# MegaShield-thruhole.net
KiCad netlist of a schematic drawn in EAGLE
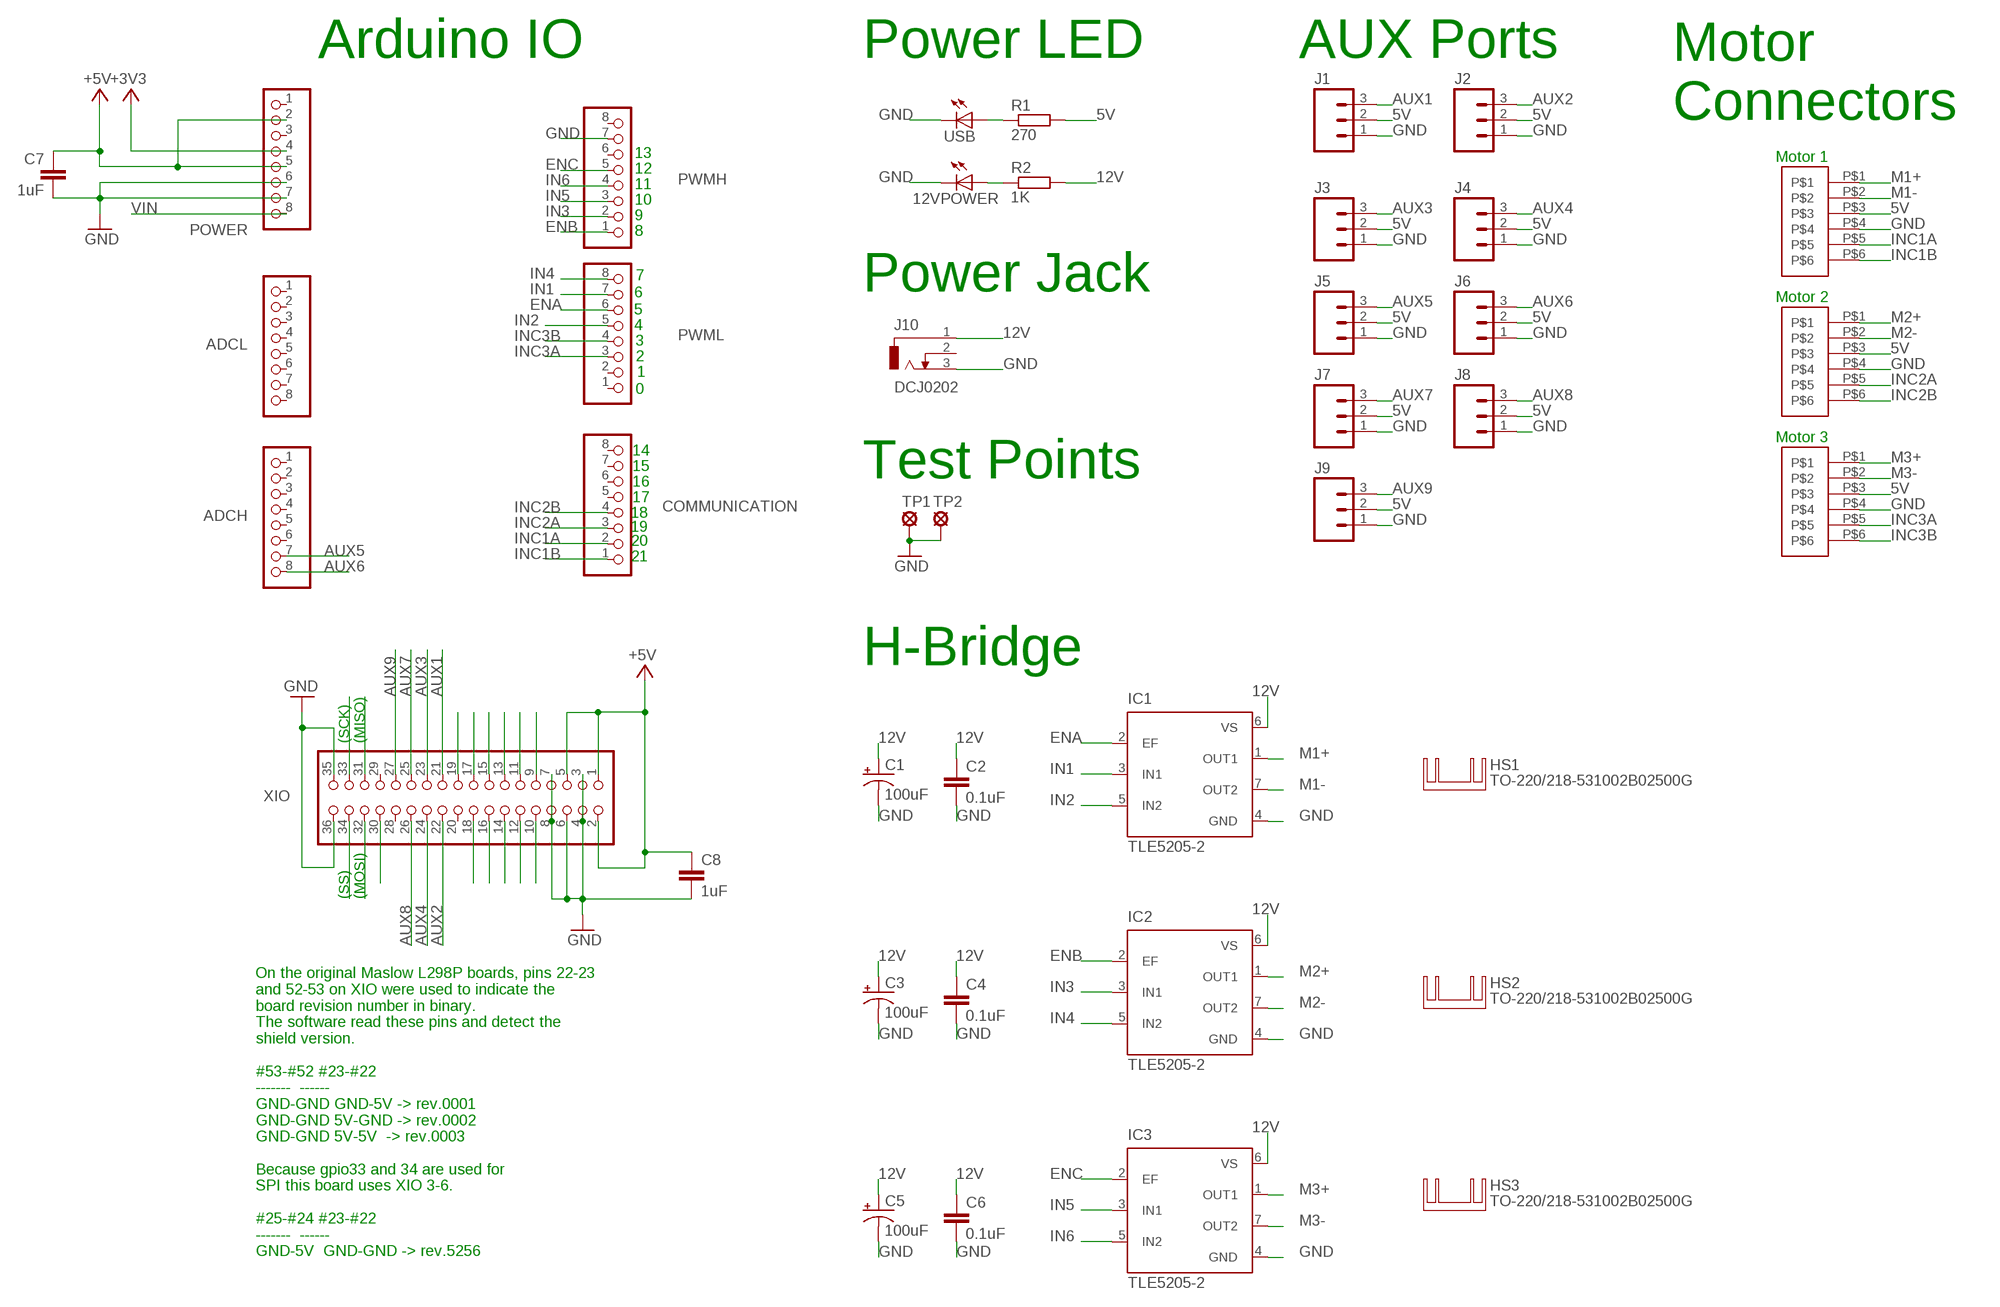
[diagram p0: schematic, sheet 1]

(export (version "E")
  (design (tool "Eeschema 10.0.6"))
  (components
    (comp (ref "12VPOWER")
      (value "LED_ELD260")
      (footprint "eagle-import:LED_LD260")
      (libsource (lib "eagle-import") (part "LED_ELD260"))
    )
    (comp (ref "ADCH")
      (value "8x1F-H8.5")
      (footprint "eagle-import:1X08")
      (libsource (lib "eagle-import") (part "PINHD-1X8"))
    )
    (comp (ref "ADCL")
      (value "PINHD-1X8")
      (footprint "eagle-import:1X08")
      (libsource (lib "eagle-import") (part "pinhead_PINHD-1X8"))
    )
    (comp (ref "C1")
      (value "100uF")
      (footprint "eagle-import:CPOL-RADIAL-100UF-25V")
      (libsource (lib "eagle-import") (part "CAP_POLPTH1"))
    )
    (comp (ref "C2")
      (value "0.1uF")
      (footprint "eagle-import:CAP-PTH-SMALL")
      (libsource (lib "eagle-import") (part "CAPPTH"))
    )
    (comp (ref "C3")
      (value "100uF")
      (footprint "eagle-import:CPOL-RADIAL-100UF-25V")
      (libsource (lib "eagle-import") (part "CAP_POLPTH1"))
    )
    (comp (ref "C4")
      (value "0.1uF")
      (footprint "eagle-import:CAP-PTH-SMALL")
      (libsource (lib "eagle-import") (part "CAPPTH"))
    )
    (comp (ref "C5")
      (value "100uF")
      (footprint "eagle-import:CPOL-RADIAL-100UF-25V")
      (libsource (lib "eagle-import") (part "CAP_POLPTH1"))
    )
    (comp (ref "C6")
      (value "0.1uF")
      (footprint "eagle-import:CAP-PTH-SMALL")
      (libsource (lib "eagle-import") (part "CAPPTH"))
    )
    (comp (ref "C7")
      (value "1uF")
      (footprint "eagle-import:CAP-PTH-SMALL")
      (libsource (lib "eagle-import") (part "CAPPTH"))
    )
    (comp (ref "C8")
      (value "1uF")
      (footprint "eagle-import:CAP-PTH-SMALL")
      (libsource (lib "eagle-import") (part "CAPPTH"))
    )
    (comp (ref "COMMUNICATION")
      (value "PINHD-1X8")
      (footprint "eagle-import:1X08")
      (libsource (lib "eagle-import") (part "pinhead_PINHD-1X8"))
    )
    (comp (ref "HS1")
      (value "TO-220/218-531002B02500G")
      (footprint "eagle-import:531XXXXXXXX")
      (libsource (lib "eagle-import") (part "TO-220/218-531XXXXXXXX"))
    )
    (comp (ref "HS2")
      (value "TO-220/218-531002B02500G")
      (footprint "eagle-import:531XXXXXXXX")
      (libsource (lib "eagle-import") (part "TO-220/218-531XXXXXXXX"))
    )
    (comp (ref "HS3")
      (value "TO-220/218-531002B02500G")
      (footprint "eagle-import:531XXXXXXXX")
      (libsource (lib "eagle-import") (part "TO-220/218-531XXXXXXXX"))
    )
    (comp (ref "IC1")
      (value "TLE5205-2")
      (footprint "eagle-import:P-TO220-7-11")
      (libsource (lib "eagle-import") (part "TLE5205-2"))
    )
    (comp (ref "IC2")
      (value "TLE5205-2")
      (footprint "eagle-import:P-TO220-7-11")
      (libsource (lib "eagle-import") (part "TLE5205-2"))
    )
    (comp (ref "IC3")
      (value "TLE5205-2")
      (footprint "eagle-import:P-TO220-7-11")
      (libsource (lib "eagle-import") (part "TLE5205-2"))
    )
    (comp (ref "J1")
      (value "M03LOCK")
      (footprint "eagle-import:1X03_LOCK")
      (libsource (lib "eagle-import") (part "M03LOCK"))
    )
    (comp (ref "J2")
      (value "M03LOCK")
      (footprint "eagle-import:1X03_LOCK")
      (libsource (lib "eagle-import") (part "M03LOCK"))
    )
    (comp (ref "J3")
      (value "M03LOCK")
      (footprint "eagle-import:1X03_LOCK")
      (libsource (lib "eagle-import") (part "M03LOCK"))
    )
    (comp (ref "J4")
      (value "M03LOCK")
      (footprint "eagle-import:1X03_LOCK")
      (libsource (lib "eagle-import") (part "M03LOCK"))
    )
    (comp (ref "J5")
      (value "M03LOCK")
      (footprint "eagle-import:1X03_LOCK")
      (libsource (lib "eagle-import") (part "M03LOCK"))
    )
    (comp (ref "J6")
      (value "M03LOCK")
      (footprint "eagle-import:1X03_LOCK")
      (libsource (lib "eagle-import") (part "M03LOCK"))
    )
    (comp (ref "J7")
      (value "M03LOCK")
      (footprint "eagle-import:1X03_LOCK")
      (libsource (lib "eagle-import") (part "M03LOCK"))
    )
    (comp (ref "J8")
      (value "M03LOCK")
      (footprint "eagle-import:1X03_LOCK")
      (libsource (lib "eagle-import") (part "M03LOCK"))
    )
    (comp (ref "J9")
      (value "M03LOCK")
      (footprint "eagle-import:1X03_LOCK")
      (libsource (lib "eagle-import") (part "M03LOCK"))
    )
    (comp (ref "J10")
      (value "DCJ0202")
      (footprint "eagle-import:DCJ0202")
      (libsource (lib "eagle-import") (part "DCJ0202"))
    )
    (comp (ref "MP1")
      (value "JST-PH-6")
      (footprint "eagle-import:JST-PHR-6-SMD")
      (libsource (lib "eagle-import") (part "JST-PH-6"))
    )
    (comp (ref "MP2")
      (value "JST-PH-6")
      (footprint "eagle-import:JST-PHR-6-SMD")
      (libsource (lib "eagle-import") (part "JST-PH-6"))
    )
    (comp (ref "MP3")
      (value "JST-PH-6")
      (footprint "eagle-import:JST-PHR-6-SMD")
      (libsource (lib "eagle-import") (part "JST-PH-6"))
    )
    (comp (ref "POWER")
      (value "8x1F-H8.5")
      (footprint "eagle-import:1X08")
      (libsource (lib "eagle-import") (part "PINHD-1X8"))
    )
    (comp (ref "PWMH")
      (value "PINHD-1X8")
      (footprint "eagle-import:1X08")
      (libsource (lib "eagle-import") (part "pinhead_PINHD-1X8"))
    )
    (comp (ref "PWML")
      (value "PINHD-1X8")
      (footprint "eagle-import:1X08")
      (libsource (lib "eagle-import") (part "pinhead_PINHD-1X8"))
    )
    (comp (ref "R1")
      (value "270")
      (footprint "eagle-import:0207_10")
      (libsource (lib "eagle-import") (part "R0207/10"))
    )
    (comp (ref "R2")
      (value "1K")
      (footprint "eagle-import:0207_10")
      (libsource (lib "eagle-import") (part "R0207/10"))
    )
    (comp (ref "TP1")
      (value "LSP10")
      (footprint "eagle-import:LSP10")
      (libsource (lib "eagle-import") (part "LSP10"))
    )
    (comp (ref "TP2")
      (value "LSP10")
      (footprint "eagle-import:LSP10")
      (libsource (lib "eagle-import") (part "LSP10"))
    )
    (comp (ref "USB")
      (value "LED_ELD260")
      (footprint "eagle-import:LED_LD260")
      (libsource (lib "eagle-import") (part "LED_ELD260"))
    )
    (comp (ref "XIO")
      (value "18x2F-H8.5")
      (footprint "eagle-import:2X18")
      (libsource (lib "eagle-import") (part "PINHD-2X18"))
    )
  )
  (nets
    (net (code "1") (name "+3V3") (class "Default")
      (node (ref "POWER") (pin "4") (pinfunction "4_4") (pintype "passive"))
    )
    (net (code "2") (name "+5V") (class "Default")
      (node (ref "C7") (pin "1") (pinfunction "1_1") (pintype "passive"))
      (node (ref "C8") (pin "1") (pinfunction "1_1") (pintype "passive"))
      (node (ref "J1") (pin "2") (pinfunction "2_2") (pintype "passive"))
      (node (ref "J2") (pin "2") (pinfunction "2_2") (pintype "passive"))
      (node (ref "J3") (pin "2") (pinfunction "2_2") (pintype "passive"))
      (node (ref "J4") (pin "2") (pinfunction "2_2") (pintype "passive"))
      (node (ref "J5") (pin "2") (pinfunction "2_2") (pintype "passive"))
      (node (ref "J6") (pin "2") (pinfunction "2_2") (pintype "passive"))
      (node (ref "J7") (pin "2") (pinfunction "2_2") (pintype "passive"))
      (node (ref "J8") (pin "2") (pinfunction "2_2") (pintype "passive"))
      (node (ref "J9") (pin "2") (pinfunction "2_2") (pintype "passive"))
      (node (ref "MP1") (pin "P$3") (pinfunction "P$3_P$3") (pintype "bidirectional"))
      (node (ref "MP2") (pin "P$3") (pinfunction "P$3_P$3") (pintype "bidirectional"))
      (node (ref "MP3") (pin "P$3") (pinfunction "P$3_P$3") (pintype "bidirectional"))
      (node (ref "POWER") (pin "2") (pinfunction "2_2") (pintype "passive"))
      (node (ref "POWER") (pin "5") (pinfunction "5_5") (pintype "passive"))
      (node (ref "R1") (pin "2") (pinfunction "2_2") (pintype "passive"))
      (node (ref "XIO") (pin "1") (pinfunction "1_1") (pintype "passive"))
      (node (ref "XIO") (pin "2") (pinfunction "2_2") (pintype "passive"))
      (node (ref "XIO") (pin "5") (pinfunction "5_5") (pintype "passive"))
    )
    (net (code "3") (name "/12V") (class "Default")
      (node (ref "C1") (pin "1") (pinfunction "+_1") (pintype "passive"))
      (node (ref "C2") (pin "1") (pinfunction "1_1") (pintype "passive"))
      (node (ref "C3") (pin "1") (pinfunction "+_1") (pintype "passive"))
      (node (ref "C4") (pin "1") (pinfunction "1_1") (pintype "passive"))
      (node (ref "C5") (pin "1") (pinfunction "+_1") (pintype "passive"))
      (node (ref "C6") (pin "1") (pinfunction "1_1") (pintype "passive"))
      (node (ref "IC1") (pin "6") (pinfunction "VS_6") (pintype "input"))
      (node (ref "IC2") (pin "6") (pinfunction "VS_6") (pintype "input"))
      (node (ref "IC3") (pin "6") (pinfunction "VS_6") (pintype "input"))
      (node (ref "J10") (pin "1") (pinfunction "1_1") (pintype "passive"))
      (node (ref "R2") (pin "2") (pinfunction "2_2") (pintype "passive"))
    )
    (net (code "4") (name "/AUX1") (class "Default")
      (node (ref "J1") (pin "3") (pinfunction "3_3") (pintype "passive"))
      (node (ref "XIO") (pin "21") (pinfunction "21_21") (pintype "passive"))
    )
    (net (code "5") (name "/AUX2") (class "Default")
      (node (ref "J2") (pin "3") (pinfunction "3_3") (pintype "passive"))
      (node (ref "XIO") (pin "22") (pinfunction "22_22") (pintype "passive"))
    )
    (net (code "6") (name "/AUX3") (class "Default")
      (node (ref "J3") (pin "3") (pinfunction "3_3") (pintype "passive"))
      (node (ref "XIO") (pin "23") (pinfunction "23_23") (pintype "passive"))
    )
    (net (code "7") (name "/AUX4") (class "Default")
      (node (ref "J4") (pin "3") (pinfunction "3_3") (pintype "passive"))
      (node (ref "XIO") (pin "24") (pinfunction "24_24") (pintype "passive"))
    )
    (net (code "8") (name "/AUX5") (class "Default")
      (node (ref "ADCH") (pin "7") (pinfunction "7_7") (pintype "passive"))
      (node (ref "J5") (pin "3") (pinfunction "3_3") (pintype "passive"))
    )
    (net (code "9") (name "/AUX6") (class "Default")
      (node (ref "ADCH") (pin "8") (pinfunction "8_8") (pintype "passive"))
      (node (ref "J6") (pin "3") (pinfunction "3_3") (pintype "passive"))
    )
    (net (code "10") (name "/AUX7") (class "Default")
      (node (ref "J7") (pin "3") (pinfunction "3_3") (pintype "passive"))
      (node (ref "XIO") (pin "25") (pinfunction "25_25") (pintype "passive"))
    )
    (net (code "11") (name "/AUX8") (class "Default")
      (node (ref "J8") (pin "3") (pinfunction "3_3") (pintype "passive"))
      (node (ref "XIO") (pin "26") (pinfunction "26_26") (pintype "passive"))
    )
    (net (code "12") (name "/AUX9") (class "Default")
      (node (ref "J9") (pin "3") (pinfunction "3_3") (pintype "passive"))
      (node (ref "XIO") (pin "27") (pinfunction "27_27") (pintype "passive"))
    )
    (net (code "13") (name "/ENA") (class "Default")
      (node (ref "IC1") (pin "2") (pinfunction "EF_2") (pintype "open_collector"))
      (node (ref "PWML") (pin "6") (pinfunction "6_6") (pintype "passive"))
    )
    (net (code "14") (name "/ENB") (class "Default")
      (node (ref "IC2") (pin "2") (pinfunction "EF_2") (pintype "open_collector"))
      (node (ref "PWMH") (pin "1") (pinfunction "1_1") (pintype "passive"))
    )
    (net (code "15") (name "/ENC") (class "Default")
      (node (ref "IC3") (pin "2") (pinfunction "EF_2") (pintype "open_collector"))
      (node (ref "PWMH") (pin "5") (pinfunction "5_5") (pintype "passive"))
    )
    (net (code "16") (name "/IN1") (class "Default")
      (node (ref "IC1") (pin "3") (pinfunction "IN1_3") (pintype "input"))
      (node (ref "PWML") (pin "7") (pinfunction "7_7") (pintype "passive"))
    )
    (net (code "17") (name "/IN2") (class "Default")
      (node (ref "IC1") (pin "5") (pinfunction "IN2_5") (pintype "input"))
      (node (ref "PWML") (pin "5") (pinfunction "5_5") (pintype "passive"))
    )
    (net (code "18") (name "/IN3") (class "Default")
      (node (ref "IC2") (pin "3") (pinfunction "IN1_3") (pintype "input"))
      (node (ref "PWMH") (pin "2") (pinfunction "2_2") (pintype "passive"))
    )
    (net (code "19") (name "/IN4") (class "Default")
      (node (ref "IC2") (pin "5") (pinfunction "IN2_5") (pintype "input"))
      (node (ref "PWML") (pin "8") (pinfunction "8_8") (pintype "passive"))
    )
    (net (code "20") (name "/IN5") (class "Default")
      (node (ref "IC3") (pin "3") (pinfunction "IN1_3") (pintype "input"))
      (node (ref "PWMH") (pin "3") (pinfunction "3_3") (pintype "passive"))
    )
    (net (code "21") (name "/IN6") (class "Default")
      (node (ref "IC3") (pin "5") (pinfunction "IN2_5") (pintype "input"))
      (node (ref "PWMH") (pin "4") (pinfunction "4_4") (pintype "passive"))
    )
    (net (code "22") (name "/INC1A") (class "Default")
      (node (ref "COMMUNICATION") (pin "2") (pinfunction "2_2") (pintype "passive"))
      (node (ref "MP1") (pin "P$5") (pinfunction "P$5_P$5") (pintype "bidirectional"))
    )
    (net (code "23") (name "/INC1B") (class "Default")
      (node (ref "COMMUNICATION") (pin "1") (pinfunction "1_1") (pintype "passive"))
      (node (ref "MP1") (pin "P$6") (pinfunction "P$6_P$6") (pintype "bidirectional"))
    )
    (net (code "24") (name "/INC2A") (class "Default")
      (node (ref "COMMUNICATION") (pin "3") (pinfunction "3_3") (pintype "passive"))
      (node (ref "MP2") (pin "P$5") (pinfunction "P$5_P$5") (pintype "bidirectional"))
    )
    (net (code "25") (name "/INC2B") (class "Default")
      (node (ref "COMMUNICATION") (pin "4") (pinfunction "4_4") (pintype "passive"))
      (node (ref "MP2") (pin "P$6") (pinfunction "P$6_P$6") (pintype "bidirectional"))
    )
    (net (code "26") (name "/INC3A") (class "Default")
      (node (ref "MP3") (pin "P$5") (pinfunction "P$5_P$5") (pintype "bidirectional"))
      (node (ref "PWML") (pin "3") (pinfunction "3_3") (pintype "passive"))
    )
    (net (code "27") (name "/INC3B") (class "Default")
      (node (ref "MP3") (pin "P$6") (pinfunction "P$6_P$6") (pintype "bidirectional"))
      (node (ref "PWML") (pin "4") (pinfunction "4_4") (pintype "passive"))
    )
    (net (code "28") (name "/M1+") (class "Default")
      (node (ref "IC1") (pin "1") (pinfunction "OUT1_1") (pintype "output"))
      (node (ref "MP1") (pin "P$1") (pinfunction "P$1_P$1") (pintype "bidirectional"))
    )
    (net (code "29") (name "/M1-") (class "Default")
      (node (ref "IC1") (pin "7") (pinfunction "OUT2_7") (pintype "output"))
      (node (ref "MP1") (pin "P$2") (pinfunction "P$2_P$2") (pintype "bidirectional"))
    )
    (net (code "30") (name "/M2+") (class "Default")
      (node (ref "IC2") (pin "1") (pinfunction "OUT1_1") (pintype "output"))
      (node (ref "MP2") (pin "P$1") (pinfunction "P$1_P$1") (pintype "bidirectional"))
    )
    (net (code "31") (name "/M2-") (class "Default")
      (node (ref "IC2") (pin "7") (pinfunction "OUT2_7") (pintype "output"))
      (node (ref "MP2") (pin "P$2") (pinfunction "P$2_P$2") (pintype "bidirectional"))
    )
    (net (code "32") (name "/M3+") (class "Default")
      (node (ref "IC3") (pin "1") (pinfunction "OUT1_1") (pintype "output"))
      (node (ref "MP3") (pin "P$1") (pinfunction "P$1_P$1") (pintype "bidirectional"))
    )
    (net (code "33") (name "/M3-") (class "Default")
      (node (ref "IC3") (pin "7") (pinfunction "OUT2_7") (pintype "output"))
      (node (ref "MP3") (pin "P$2") (pinfunction "P$2_P$2") (pintype "bidirectional"))
    )
    (net (code "34") (name "/VIN") (class "Default")
      (node (ref "POWER") (pin "8") (pinfunction "8_8") (pintype "passive"))
    )
    (net (code "35") (name "GND") (class "Default")
      (node (ref "12VPOWER") (pin "K") (pinfunction "C_K") (pintype "passive"))
      (node (ref "C1") (pin "2") (pinfunction "-_2") (pintype "passive"))
      (node (ref "C2") (pin "2") (pinfunction "2_2") (pintype "passive"))
      (node (ref "C3") (pin "2") (pinfunction "-_2") (pintype "passive"))
      (node (ref "C4") (pin "2") (pinfunction "2_2") (pintype "passive"))
      (node (ref "C5") (pin "2") (pinfunction "-_2") (pintype "passive"))
      (node (ref "C6") (pin "2") (pinfunction "2_2") (pintype "passive"))
      (node (ref "C7") (pin "2") (pinfunction "2_2") (pintype "passive"))
      (node (ref "C8") (pin "2") (pinfunction "2_2") (pintype "passive"))
      (node (ref "IC1") (pin "4") (pinfunction "GND_4") (pintype "power_in"))
      (node (ref "IC2") (pin "4") (pinfunction "GND_4") (pintype "power_in"))
      (node (ref "IC3") (pin "4") (pinfunction "GND_4") (pintype "power_in"))
      (node (ref "J1") (pin "1") (pinfunction "1_1") (pintype "passive"))
      (node (ref "J10") (pin "3") (pinfunction "3_3") (pintype "passive"))
      (node (ref "J2") (pin "1") (pinfunction "1_1") (pintype "passive"))
      (node (ref "J3") (pin "1") (pinfunction "1_1") (pintype "passive"))
      (node (ref "J4") (pin "1") (pinfunction "1_1") (pintype "passive"))
      (node (ref "J5") (pin "1") (pinfunction "1_1") (pintype "passive"))
      (node (ref "J6") (pin "1") (pinfunction "1_1") (pintype "passive"))
      (node (ref "J7") (pin "1") (pinfunction "1_1") (pintype "passive"))
      (node (ref "J8") (pin "1") (pinfunction "1_1") (pintype "passive"))
      (node (ref "J9") (pin "1") (pinfunction "1_1") (pintype "passive"))
      (node (ref "MP1") (pin "P$4") (pinfunction "P$4_P$4") (pintype "bidirectional"))
      (node (ref "MP2") (pin "P$4") (pinfunction "P$4_P$4") (pintype "bidirectional"))
      (node (ref "MP3") (pin "P$4") (pinfunction "P$4_P$4") (pintype "bidirectional"))
      (node (ref "POWER") (pin "6") (pinfunction "6_6") (pintype "passive"))
      (node (ref "POWER") (pin "7") (pinfunction "7_7") (pintype "passive"))
      (node (ref "PWMH") (pin "7") (pinfunction "7_7") (pintype "passive"))
      (node (ref "TP1") (pin "MP") (pinfunction "MP_MP") (pintype "passive"))
      (node (ref "TP2") (pin "MP") (pinfunction "MP_MP") (pintype "passive"))
      (node (ref "USB") (pin "K") (pinfunction "C_K") (pintype "passive"))
      (node (ref "XIO") (pin "3") (pinfunction "3_3") (pintype "passive"))
      (node (ref "XIO") (pin "35") (pinfunction "35_35") (pintype "passive"))
      (node (ref "XIO") (pin "36") (pinfunction "36_36") (pintype "passive"))
      (node (ref "XIO") (pin "4") (pinfunction "4_4") (pintype "passive"))
      (node (ref "XIO") (pin "6") (pinfunction "6_6") (pintype "passive"))
      (node (ref "XIO") (pin "7") (pinfunction "7_7") (pintype "passive"))
      (node (ref "XIO") (pin "8") (pinfunction "8_8") (pintype "passive"))
    )
    (net (code "36") (name "Net-(12VPOWER-PadA)") (class "Default")
      (node (ref "12VPOWER") (pin "A") (pinfunction "A_A") (pintype "passive"))
      (node (ref "R2") (pin "1") (pinfunction "1_1") (pintype "passive"))
    )
    (net (code "37") (name "Net-(R1-Pad1)") (class "Default")
      (node (ref "R1") (pin "1") (pinfunction "1_1") (pintype "passive"))
      (node (ref "USB") (pin "A") (pinfunction "A_A") (pintype "passive"))
    )
    (net (code "38") (name "unconnected-(ADCH-Pad1)") (class "Default")
      (node (ref "ADCH") (pin "1") (pinfunction "1_1") (pintype "passive"))
    )
    (net (code "39") (name "unconnected-(ADCH-Pad2)") (class "Default")
      (node (ref "ADCH") (pin "2") (pinfunction "2_2") (pintype "passive"))
    )
    (net (code "40") (name "unconnected-(ADCH-Pad3)") (class "Default")
      (node (ref "ADCH") (pin "3") (pinfunction "3_3") (pintype "passive"))
    )
    (net (code "41") (name "unconnected-(ADCH-Pad4)") (class "Default")
      (node (ref "ADCH") (pin "4") (pinfunction "4_4") (pintype "passive"))
    )
    (net (code "42") (name "unconnected-(ADCH-Pad5)") (class "Default")
      (node (ref "ADCH") (pin "5") (pinfunction "5_5") (pintype "passive"))
    )
    (net (code "43") (name "unconnected-(ADCH-Pad6)") (class "Default")
      (node (ref "ADCH") (pin "6") (pinfunction "6_6") (pintype "passive"))
    )
    (net (code "44") (name "unconnected-(ADCL-Pad1)") (class "Default")
      (node (ref "ADCL") (pin "1") (pinfunction "1_1") (pintype "passive"))
    )
    (net (code "45") (name "unconnected-(ADCL-Pad2)") (class "Default")
      (node (ref "ADCL") (pin "2") (pinfunction "2_2") (pintype "passive"))
    )
    (net (code "46") (name "unconnected-(ADCL-Pad3)") (class "Default")
      (node (ref "ADCL") (pin "3") (pinfunction "3_3") (pintype "passive"))
    )
    (net (code "47") (name "unconnected-(ADCL-Pad4)") (class "Default")
      (node (ref "ADCL") (pin "4") (pinfunction "4_4") (pintype "passive"))
    )
    (net (code "48") (name "unconnected-(ADCL-Pad5)") (class "Default")
      (node (ref "ADCL") (pin "5") (pinfunction "5_5") (pintype "passive"))
    )
    (net (code "49") (name "unconnected-(ADCL-Pad6)") (class "Default")
      (node (ref "ADCL") (pin "6") (pinfunction "6_6") (pintype "passive"))
    )
    (net (code "50") (name "unconnected-(ADCL-Pad7)") (class "Default")
      (node (ref "ADCL") (pin "7") (pinfunction "7_7") (pintype "passive"))
    )
    (net (code "51") (name "unconnected-(ADCL-Pad8)") (class "Default")
      (node (ref "ADCL") (pin "8") (pinfunction "8_8") (pintype "passive"))
    )
    (net (code "52") (name "unconnected-(COMMUNICATION-Pad5)") (class "Default")
      (node (ref "COMMUNICATION") (pin "5") (pinfunction "5_5") (pintype "passive"))
    )
    (net (code "53") (name "unconnected-(COMMUNICATION-Pad6)") (class "Default")
      (node (ref "COMMUNICATION") (pin "6") (pinfunction "6_6") (pintype "passive"))
    )
    (net (code "54") (name "unconnected-(COMMUNICATION-Pad7)") (class "Default")
      (node (ref "COMMUNICATION") (pin "7") (pinfunction "7_7") (pintype "passive"))
    )
    (net (code "55") (name "unconnected-(COMMUNICATION-Pad8)") (class "Default")
      (node (ref "COMMUNICATION") (pin "8") (pinfunction "8_8") (pintype "passive"))
    )
    (net (code "56") (name "unconnected-(J10-Pad2)") (class "Default")
      (node (ref "J10") (pin "2") (pinfunction "2_2") (pintype "passive"))
    )
    (net (code "57") (name "unconnected-(POWER-Pad1)") (class "Default")
      (node (ref "POWER") (pin "1") (pinfunction "1_1") (pintype "passive"))
    )
    (net (code "58") (name "unconnected-(POWER-Pad3)") (class "Default")
      (node (ref "POWER") (pin "3") (pinfunction "3_3") (pintype "passive"))
    )
    (net (code "59") (name "unconnected-(PWMH-Pad6)") (class "Default")
      (node (ref "PWMH") (pin "6") (pinfunction "6_6") (pintype "passive"))
    )
    (net (code "60") (name "unconnected-(PWMH-Pad8)") (class "Default")
      (node (ref "PWMH") (pin "8") (pinfunction "8_8") (pintype "passive"))
    )
    (net (code "61") (name "unconnected-(PWML-Pad1)") (class "Default")
      (node (ref "PWML") (pin "1") (pinfunction "1_1") (pintype "passive"))
    )
    (net (code "62") (name "unconnected-(PWML-Pad2)") (class "Default")
      (node (ref "PWML") (pin "2") (pinfunction "2_2") (pintype "passive"))
    )
    (net (code "63") (name "unconnected-(XIO-Pad9)") (class "Default")
      (node (ref "XIO") (pin "9") (pinfunction "9_9") (pintype "passive"))
    )
    (net (code "64") (name "unconnected-(XIO-Pad10)") (class "Default")
      (node (ref "XIO") (pin "10") (pinfunction "10_10") (pintype "passive"))
    )
    (net (code "65") (name "unconnected-(XIO-Pad11)") (class "Default")
      (node (ref "XIO") (pin "11") (pinfunction "11_11") (pintype "passive"))
    )
    (net (code "66") (name "unconnected-(XIO-Pad12)") (class "Default")
      (node (ref "XIO") (pin "12") (pinfunction "12_12") (pintype "passive"))
    )
    (net (code "67") (name "unconnected-(XIO-Pad13)") (class "Default")
      (node (ref "XIO") (pin "13") (pinfunction "13_13") (pintype "passive"))
    )
    (net (code "68") (name "unconnected-(XIO-Pad14)") (class "Default")
      (node (ref "XIO") (pin "14") (pinfunction "14_14") (pintype "passive"))
    )
    (net (code "69") (name "unconnected-(XIO-Pad15)") (class "Default")
      (node (ref "XIO") (pin "15") (pinfunction "15_15") (pintype "passive"))
    )
    (net (code "70") (name "unconnected-(XIO-Pad16)") (class "Default")
      (node (ref "XIO") (pin "16") (pinfunction "16_16") (pintype "passive"))
    )
    (net (code "71") (name "unconnected-(XIO-Pad17)") (class "Default")
      (node (ref "XIO") (pin "17") (pinfunction "17_17") (pintype "passive"))
    )
    (net (code "72") (name "unconnected-(XIO-Pad18)") (class "Default")
      (node (ref "XIO") (pin "18") (pinfunction "18_18") (pintype "passive"))
    )
    (net (code "73") (name "unconnected-(XIO-Pad19)") (class "Default")
      (node (ref "XIO") (pin "19") (pinfunction "19_19") (pintype "passive"))
    )
    (net (code "74") (name "unconnected-(XIO-Pad20)") (class "Default")
      (node (ref "XIO") (pin "20") (pinfunction "20_20") (pintype "passive"))
    )
    (net (code "75") (name "unconnected-(XIO-Pad28)") (class "Default")
      (node (ref "XIO") (pin "28") (pinfunction "28_28") (pintype "passive"))
    )
    (net (code "76") (name "unconnected-(XIO-Pad29)") (class "Default")
      (node (ref "XIO") (pin "29") (pinfunction "29_29") (pintype "passive"))
    )
    (net (code "77") (name "unconnected-(XIO-Pad30)") (class "Default")
      (node (ref "XIO") (pin "30") (pinfunction "30_30") (pintype "passive"))
    )
    (net (code "78") (name "unconnected-(XIO-Pad31)") (class "Default")
      (node (ref "XIO") (pin "31") (pinfunction "31_31") (pintype "passive"))
    )
    (net (code "79") (name "unconnected-(XIO-Pad32)") (class "Default")
      (node (ref "XIO") (pin "32") (pinfunction "32_32") (pintype "passive"))
    )
    (net (code "80") (name "unconnected-(XIO-Pad33)") (class "Default")
      (node (ref "XIO") (pin "33") (pinfunction "33_33") (pintype "passive"))
    )
    (net (code "81") (name "unconnected-(XIO-Pad34)") (class "Default")
      (node (ref "XIO") (pin "34") (pinfunction "34_34") (pintype "passive"))
    )
  )
)
